# schematic-ebook-reader_v43.net
KiCad netlist of a schematic drawn in EAGLE
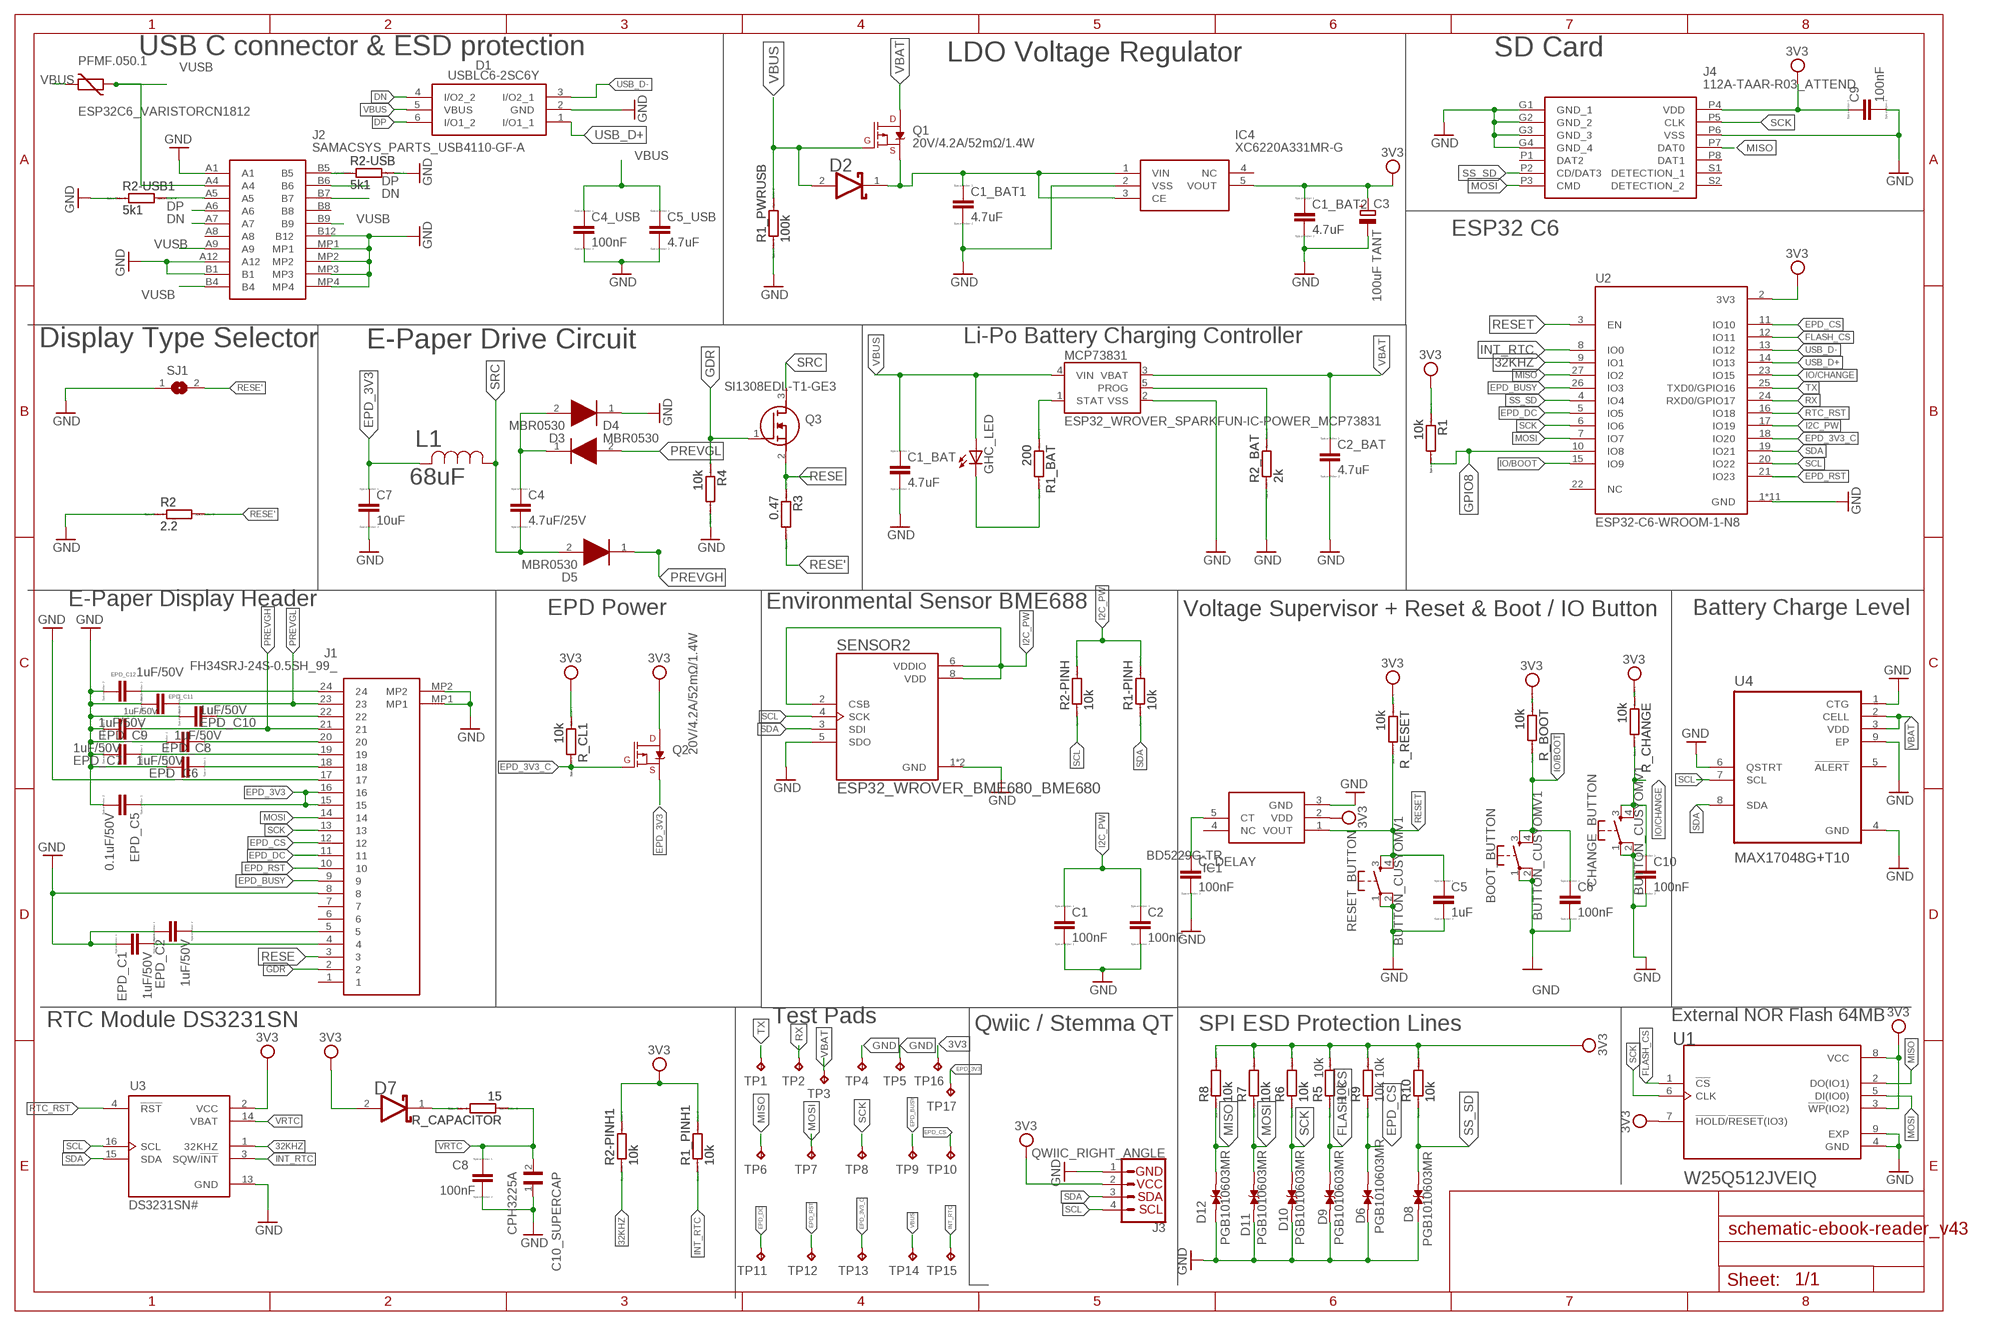
[diagram p0: schematic, sheet 1]

(export (version "E")
  (design (tool "Eeschema 10.0.6"))
  (components
    (comp (ref "BOOT_BUTTON")
      (value "BUTTON_CUSYOMV1")
      (footprint "eagle-import:MYBUTTON")
      (libsource (lib "eagle-import") (part "BUTTON_CUSYOMV1"))
    )
    (comp (ref "C1")
      (value "100nF")
      (footprint "eagle-import:ESP32_WROVER_EAGLE-LTSPICE_C0402")
      (libsource (lib "eagle-import") (part "ESP32_WROVER_EAGLE-LTSPICE_CC0402"))
    )
    (comp (ref "C1_BAT")
      (value "4.7uF")
      (footprint "eagle-import:ESP32_WROVER_EAGLE-LTSPICE_C0402")
      (libsource (lib "eagle-import") (part "ESP32_WROVER_EAGLE-LTSPICE_CC0402"))
    )
    (comp (ref "C1_BAT1")
      (value "4.7uF")
      (footprint "eagle-import:ESP32_WROVER_EAGLE-LTSPICE_C0402")
      (libsource (lib "eagle-import") (part "ESP32_WROVER_EAGLE-LTSPICE_CC0402"))
    )
    (comp (ref "C1_BAT2")
      (value "4.7uF")
      (footprint "eagle-import:ESP32_WROVER_EAGLE-LTSPICE_C0402")
      (libsource (lib "eagle-import") (part "ESP32_WROVER_EAGLE-LTSPICE_CC0402"))
    )
    (comp (ref "C2")
      (value "100nF")
      (footprint "eagle-import:ESP32_WROVER_EAGLE-LTSPICE_C0402")
      (libsource (lib "eagle-import") (part "ESP32_WROVER_EAGLE-LTSPICE_CC0402"))
    )
    (comp (ref "C2_BAT")
      (value "4.7uF")
      (footprint "eagle-import:ESP32_WROVER_EAGLE-LTSPICE_C0402")
      (libsource (lib "eagle-import") (part "ESP32_WROVER_EAGLE-LTSPICE_CC0402"))
    )
    (comp (ref "C3")
      (value "100uF TANT")
      (footprint "eagle-import:RCL_CT3528")
      (libsource (lib "eagle-import") (part "RCL_CPOL-EUCT3528"))
    )
    (comp (ref "C4")
      (value "4.7uF/25V")
      (footprint "eagle-import:ESP32_WROVER_EAGLE-LTSPICE_C0402")
      (libsource (lib "eagle-import") (part "ESP32_WROVER_EAGLE-LTSPICE_CC0402"))
    )
    (comp (ref "C4_USB")
      (value "100nF")
      (footprint "eagle-import:ESP32_WROVER_EAGLE-LTSPICE_C0402")
      (libsource (lib "eagle-import") (part "ESP32_WROVER_EAGLE-LTSPICE_CC0402"))
    )
    (comp (ref "C5")
      (value "1uF")
      (footprint "eagle-import:ESP32_WROVER_EAGLE-LTSPICE_C0402")
      (libsource (lib "eagle-import") (part "ESP32_WROVER_EAGLE-LTSPICE_CC0402"))
    )
    (comp (ref "C5_USB")
      (value "4.7uF")
      (footprint "eagle-import:ESP32_WROVER_EAGLE-LTSPICE_C0402")
      (libsource (lib "eagle-import") (part "ESP32_WROVER_EAGLE-LTSPICE_CC0402"))
    )
    (comp (ref "C6")
      (value "100nF")
      (footprint "eagle-import:ESP32_WROVER_EAGLE-LTSPICE_C0402")
      (libsource (lib "eagle-import") (part "ESP32_WROVER_EAGLE-LTSPICE_CC0402"))
    )
    (comp (ref "C7")
      (value "10uF")
      (footprint "eagle-import:ESP32_WROVER_EAGLE-LTSPICE_C0402")
      (libsource (lib "eagle-import") (part "ESP32_WROVER_EAGLE-LTSPICE_CC0402"))
    )
    (comp (ref "C8")
      (value "100nF")
      (footprint "eagle-import:ESP32_WROVER_EAGLE-LTSPICE_C0402")
      (libsource (lib "eagle-import") (part "ESP32_WROVER_EAGLE-LTSPICE_CC0402"))
    )
    (comp (ref "C9")
      (value "100nF")
      (footprint "eagle-import:ESP32_WROVER_EAGLE-LTSPICE_C0402")
      (libsource (lib "eagle-import") (part "ESP32_WROVER_EAGLE-LTSPICE_CC0402"))
    )
    (comp (ref "C10")
      (value "100nF")
      (footprint "eagle-import:ESP32_WROVER_EAGLE-LTSPICE_C0402")
      (libsource (lib "eagle-import") (part "ESP32_WROVER_EAGLE-LTSPICE_CC0402"))
    )
    (comp (ref "C10_SUPERCAP")
      (value "CPH3225A")
      (footprint "eagle-import:CAPCP3225X100N")
      (fields (field (name "MF") "Seiko Instruments"))
      (libsource (lib "eagle-import") (part "CPH3225A"))
    )
    (comp (ref "CHANGE_BUTTON")
      (value "BUTTON_CUSYOMV1")
      (footprint "eagle-import:MYBUTTON")
      (libsource (lib "eagle-import") (part "BUTTON_CUSYOMV1"))
    )
    (comp (ref "C_DELAY")
      (value "100nF")
      (footprint "eagle-import:ESP32_WROVER_EAGLE-LTSPICE_C0402")
      (libsource (lib "eagle-import") (part "ESP32_WROVER_EAGLE-LTSPICE_CC0402"))
    )
    (comp (ref "D1")
      (value "USBLC6-2SC6Y")
      (footprint "eagle-import:SOT95P280X145-6N")
      (fields (field (name "MF") "STMicroelectronics"))
      (libsource (lib "eagle-import") (part "USBLC6-2SC6Y"))
    )
    (comp (ref "D2")
      (value "ESP32_WROVER_AVX---SD0805S020S1R0_AVX_SD0805S020S1R0_0_0AVX_SD0805S020S1R0_0_0")
      (footprint "eagle-import:ESP32_WROVER_AVX---SD0805S020S1R0_AVX_SD0805S020S1R0_0")
      (fields
        (field (name "DIGIKEY_PART_NUMBER") "478-7800-1-ND")
        (field (name "MF") "AVX")
        (field (name "MOUSER_PART_NUMBER") "581-SD0805S020S1R0")
      )
      (libsource (lib "eagle-import") (part "ESP32_WROVER_AVX---SD0805S020S1R0_AVX_SD0805S020S1R0_0_0AVX_SD0805S020S1R0_0_0"))
    )
    (comp (ref "D3")
      (value "MBR0530")
      (footprint "eagle-import:SOD3716X135N")
      (fields (field (name "MF") "ON Semiconductor"))
      (libsource (lib "eagle-import") (part "MBR0530"))
    )
    (comp (ref "D4")
      (value "MBR0530")
      (footprint "eagle-import:SOD3716X135N")
      (fields (field (name "MF") "ON Semiconductor"))
      (libsource (lib "eagle-import") (part "MBR0530"))
    )
    (comp (ref "D5")
      (value "MBR0530")
      (footprint "eagle-import:SOD3716X135N")
      (fields (field (name "MF") "ON Semiconductor"))
      (libsource (lib "eagle-import") (part "MBR0530"))
    )
    (comp (ref "D6")
      (value "PGB1010603MR")
      (footprint "eagle-import:DIOC1608X36N")
      (fields (field (name "MF") "Littelfuse Inc."))
      (libsource (lib "eagle-import") (part "PGB1010603MR"))
    )
    (comp (ref "D7")
      (value "ESP32_WROVER_AVX---SD0805S020S1R0_AVX_SD0805S020S1R0_0_0AVX_SD0805S020S1R0_0_0")
      (footprint "eagle-import:ESP32_WROVER_AVX---SD0805S020S1R0_AVX_SD0805S020S1R0_0")
      (fields
        (field (name "DIGIKEY_PART_NUMBER") "478-7800-1-ND")
        (field (name "MF") "AVX")
        (field (name "MOUSER_PART_NUMBER") "581-SD0805S020S1R0")
      )
      (libsource (lib "eagle-import") (part "ESP32_WROVER_AVX---SD0805S020S1R0_AVX_SD0805S020S1R0_0_0AVX_SD0805S020S1R0_0_0"))
    )
    (comp (ref "D8")
      (value "PGB1010603MR")
      (footprint "eagle-import:DIOC1608X36N")
      (fields (field (name "MF") "Littelfuse Inc."))
      (libsource (lib "eagle-import") (part "PGB1010603MR"))
    )
    (comp (ref "D9")
      (value "PGB1010603MR")
      (footprint "eagle-import:DIOC1608X36N")
      (fields (field (name "MF") "Littelfuse Inc."))
      (libsource (lib "eagle-import") (part "PGB1010603MR"))
    )
    (comp (ref "D10")
      (value "PGB1010603MR")
      (footprint "eagle-import:DIOC1608X36N")
      (fields (field (name "MF") "Littelfuse Inc."))
      (libsource (lib "eagle-import") (part "PGB1010603MR"))
    )
    (comp (ref "D11")
      (value "PGB1010603MR")
      (footprint "eagle-import:DIOC1608X36N")
      (fields (field (name "MF") "Littelfuse Inc."))
      (libsource (lib "eagle-import") (part "PGB1010603MR"))
    )
    (comp (ref "D12")
      (value "PGB1010603MR")
      (footprint "eagle-import:DIOC1608X36N")
      (fields (field (name "MF") "Littelfuse Inc."))
      (libsource (lib "eagle-import") (part "PGB1010603MR"))
    )
    (comp (ref "EPD_C1")
      (value "1uF/50V")
      (footprint "eagle-import:ESP32_WROVER_EAGLE-LTSPICE_C0402")
      (libsource (lib "eagle-import") (part "ESP32_WROVER_EAGLE-LTSPICE_CC0402"))
    )
    (comp (ref "EPD_C2")
      (value "1uF/50V")
      (footprint "eagle-import:ESP32_WROVER_EAGLE-LTSPICE_C0402")
      (libsource (lib "eagle-import") (part "ESP32_WROVER_EAGLE-LTSPICE_CC0402"))
    )
    (comp (ref "EPD_C5")
      (value "0.1uF/50V")
      (footprint "eagle-import:ESP32_WROVER_EAGLE-LTSPICE_C0402")
      (libsource (lib "eagle-import") (part "ESP32_WROVER_EAGLE-LTSPICE_CC0402"))
    )
    (comp (ref "EPD_C6")
      (value "1uF/50V")
      (footprint "eagle-import:ESP32_WROVER_EAGLE-LTSPICE_C0402")
      (libsource (lib "eagle-import") (part "ESP32_WROVER_EAGLE-LTSPICE_CC0402"))
    )
    (comp (ref "EPD_C7")
      (value "1uF/50V")
      (footprint "eagle-import:ESP32_WROVER_EAGLE-LTSPICE_C0402")
      (libsource (lib "eagle-import") (part "ESP32_WROVER_EAGLE-LTSPICE_CC0402"))
    )
    (comp (ref "EPD_C8")
      (value "1uF/50V")
      (footprint "eagle-import:ESP32_WROVER_EAGLE-LTSPICE_C0402")
      (libsource (lib "eagle-import") (part "ESP32_WROVER_EAGLE-LTSPICE_CC0402"))
    )
    (comp (ref "EPD_C9")
      (value "1uF/50V")
      (footprint "eagle-import:ESP32_WROVER_EAGLE-LTSPICE_C0402")
      (libsource (lib "eagle-import") (part "ESP32_WROVER_EAGLE-LTSPICE_CC0402"))
    )
    (comp (ref "EPD_C10")
      (value "1uF/50V")
      (footprint "eagle-import:ESP32_WROVER_EAGLE-LTSPICE_C0402")
      (libsource (lib "eagle-import") (part "ESP32_WROVER_EAGLE-LTSPICE_CC0402"))
    )
    (comp (ref "EPD_C11")
      (value "1uF/50V")
      (footprint "eagle-import:ESP32_WROVER_EAGLE-LTSPICE_C0402")
      (libsource (lib "eagle-import") (part "ESP32_WROVER_EAGLE-LTSPICE_CC0402"))
    )
    (comp (ref "EPD_C12")
      (value "1uF/50V")
      (footprint "eagle-import:ESP32_WROVER_EAGLE-LTSPICE_C0402")
      (libsource (lib "eagle-import") (part "ESP32_WROVER_EAGLE-LTSPICE_CC0402"))
    )
    (comp (ref "GHC_LED")
      (value "ADAFRUIT_LEDCHIP-LED0603")
      (footprint "eagle-import:ADAFRUIT_CHIP-LED0603")
      (libsource (lib "eagle-import") (part "ADAFRUIT_LEDCHIP-LED0603"))
    )
    (comp (ref "IC1")
      (value "BD5229G-TR")
      (footprint "eagle-import:SOT95P280X125-5N")
      (fields (field (name "MOUSER_PART_NUMBER") "755-BD5229G-TR"))
      (libsource (lib "eagle-import") (part "BD5229G-TR"))
    )
    (comp (ref "IC4")
      (value "XC6220A331MR-G")
      (footprint "eagle-import:SOT95P280X120-5N")
      (fields (field (name "MOUSER_PART_NUMBER") "865-XC6220A331MR-G"))
      (libsource (lib "eagle-import") (part "XC6220A331MR-G"))
    )
    (comp (ref "J1")
      (value "FH34SRJ-24S-0.5SH_99_")
      (footprint "eagle-import:FH34SRJ24S05SH99")
      (fields
        (field (name "MANUFACTURER_PART_NUMBER") "FH34SRJ-24S-0.5SH(99)")
        (field (name "MOUSER_PART_NUMBER") "798-FH34SRJ24S05SH99")
      )
      (libsource (lib "eagle-import") (part "FH34SRJ-24S-0.5SH_99_"))
    )
    (comp (ref "J2")
      (value "SAMACSYS_PARTS_USB4110-GF-A")
      (footprint "eagle-import:SAMACSYS_PARTS_USB4110GFA")
      (fields
        (field (name "MANUFACTURER_PART_NUMBER") "USB4110-GF-A")
        (field (name "MOUSER_PART_NUMBER") "640-USB4110-GF-A")
      )
      (libsource (lib "eagle-import") (part "SAMACSYS_PARTS_USB4110-GF-A"))
    )
    (comp (ref "J3")
      (value "QWIIC_RIGHT_ANGLE")
      (footprint "eagle-import:JST04_1MM_RA")
      (libsource (lib "eagle-import") (part "QWIIC_CONNECTORJS-1MM"))
    )
    (comp (ref "J4")
      (value "112A-TAAR-R03_ATTEND")
      (footprint "eagle-import:112ATAARR03ATTEND")
      (fields (field (name "MANUFACTURER_PART_NUMBER") "112A-TAAR-R03 ATTEND"))
      (libsource (lib "eagle-import") (part "112A-TAAR-R03_ATTEND"))
    )
    (comp (ref "L1")
      (value "68uF")
      (footprint "eagle-import:IND_4828-WE-TPC_WRE")
      (fields
        (field (name "MANUFACTURER_PART_NUMBER") "744043680")
        (field (name "COPYRIGHT") "Copyright (C) 2024 Ultra Librarian. All rights reserved.")
      )
      (libsource (lib "eagle-import") (part "744043680IND_4828-WE-TPC_WRE"))
    )
    (comp (ref "MCP73831")
      (value "ESP32_WROVER_SPARKFUN-IC-POWER_MCP73831")
      (footprint "eagle-import:ESP32_WROVER_SPARKFUN-IC-POWER_SOT23-5")
      (libsource (lib "eagle-import") (part "ESP32_WROVER_SPARKFUN-IC-POWER_MCP73831"))
    )
    (comp (ref "PFMF.050.1")
      (value "ESP32C6_VARISTORCN1812")
      (footprint "eagle-import:ESP32C6_VARISTOR_CT_CN1812")
      (libsource (lib "eagle-import") (part "ESP32C6_VARISTORCN1812"))
    )
    (comp (ref "Q1")
      (value "20V/4.2A/52mΩ/1.4W")
      (footprint "eagle-import:ESP32_WROVER_SPARKFUN-DISCRETESEMI_SOT23-3")
      (libsource (lib "eagle-import") (part "ESP32_WROVER_SPARKFUN-DISCRETESEMI_MOSFET_PCH-DMG2305UX-7"))
    )
    (comp (ref "Q2")
      (value "20V/4.2A/52mΩ/1.4W")
      (footprint "eagle-import:ESP32_WROVER_SPARKFUN-DISCRETESEMI_SOT23-3")
      (libsource (lib "eagle-import") (part "ESP32_WROVER_SPARKFUN-DISCRETESEMI_MOSFET_PCH-DMG2305UX-7"))
    )
    (comp (ref "Q3")
      (value "SI1308EDL-T1-GE3")
      (footprint "eagle-import:SOT65P210X110-3N")
      (fields (field (name "MF") "Vishay Siliconix"))
      (libsource (lib "eagle-import") (part "SI1308EDL-T1-GE3"))
    )
    (comp (ref "R1")
      (value "10k")
      (footprint "eagle-import:ESP32_WROVER_EAGLE-LTSPICE_C0402")
      (libsource (lib "eagle-import") (part "ESP32_WROVER_EAGLE-LTSPICE_RR0402"))
    )
    (comp (ref "R1-PINH")
      (value "10k")
      (footprint "eagle-import:ESP32_WROVER_EAGLE-LTSPICE_C0402")
      (libsource (lib "eagle-import") (part "ESP32_WROVER_EAGLE-LTSPICE_RR0402"))
    )
    (comp (ref "R1_BAT")
      (value "200")
      (footprint "eagle-import:ESP32_WROVER_EAGLE-LTSPICE_C0402")
      (libsource (lib "eagle-import") (part "ESP32_WROVER_EAGLE-LTSPICE_RR0402"))
    )
    (comp (ref "R1_PINH1")
      (value "10k")
      (footprint "eagle-import:ESP32_WROVER_EAGLE-LTSPICE_C0402")
      (libsource (lib "eagle-import") (part "ESP32_WROVER_EAGLE-LTSPICE_RR0402"))
    )
    (comp (ref "R1_PWRUSB")
      (value "100k")
      (footprint "eagle-import:ESP32_WROVER_EAGLE-LTSPICE_C0402")
      (libsource (lib "eagle-import") (part "ESP32_WROVER_EAGLE-LTSPICE_RR0402"))
    )
    (comp (ref "R2")
      (value "2.2")
      (footprint "eagle-import:ESP32_WROVER_EAGLE-LTSPICE_C0402")
      (libsource (lib "eagle-import") (part "ESP32_WROVER_EAGLE-LTSPICE_RR0402"))
    )
    (comp (ref "R2-PINH")
      (value "10k")
      (footprint "eagle-import:ESP32_WROVER_EAGLE-LTSPICE_C0402")
      (libsource (lib "eagle-import") (part "ESP32_WROVER_EAGLE-LTSPICE_RR0402"))
    )
    (comp (ref "R2-PINH1")
      (value "10k")
      (footprint "eagle-import:ESP32_WROVER_EAGLE-LTSPICE_C0402")
      (libsource (lib "eagle-import") (part "ESP32_WROVER_EAGLE-LTSPICE_RR0402"))
    )
    (comp (ref "R2-USB")
      (value "5k1")
      (footprint "eagle-import:ESP32_WROVER_EAGLE-LTSPICE_C0402")
      (libsource (lib "eagle-import") (part "ESP32_WROVER_EAGLE-LTSPICE_RR0402"))
    )
    (comp (ref "R2-USB1")
      (value "5k1")
      (footprint "eagle-import:ESP32_WROVER_EAGLE-LTSPICE_C0402")
      (libsource (lib "eagle-import") (part "ESP32_WROVER_EAGLE-LTSPICE_RR0402"))
    )
    (comp (ref "R2_BAT")
      (value "2k")
      (footprint "eagle-import:ESP32_WROVER_EAGLE-LTSPICE_C0402")
      (libsource (lib "eagle-import") (part "ESP32_WROVER_EAGLE-LTSPICE_RR0402"))
    )
    (comp (ref "R3")
      (value "0.47")
      (footprint "eagle-import:ESP32_WROVER_EAGLE-LTSPICE_C0402")
      (libsource (lib "eagle-import") (part "ESP32_WROVER_EAGLE-LTSPICE_RR0402"))
    )
    (comp (ref "R4")
      (value "10k")
      (footprint "eagle-import:ESP32_WROVER_EAGLE-LTSPICE_C0402")
      (libsource (lib "eagle-import") (part "ESP32_WROVER_EAGLE-LTSPICE_RR0402"))
    )
    (comp (ref "R5")
      (value "10k")
      (footprint "eagle-import:ESP32_WROVER_EAGLE-LTSPICE_C0402")
      (libsource (lib "eagle-import") (part "ESP32_WROVER_EAGLE-LTSPICE_RR0402"))
    )
    (comp (ref "R6")
      (value "10k")
      (footprint "eagle-import:ESP32_WROVER_EAGLE-LTSPICE_C0402")
      (libsource (lib "eagle-import") (part "ESP32_WROVER_EAGLE-LTSPICE_RR0402"))
    )
    (comp (ref "R7")
      (value "10k")
      (footprint "eagle-import:ESP32_WROVER_EAGLE-LTSPICE_C0402")
      (libsource (lib "eagle-import") (part "ESP32_WROVER_EAGLE-LTSPICE_RR0402"))
    )
    (comp (ref "R8")
      (value "10k")
      (footprint "eagle-import:ESP32_WROVER_EAGLE-LTSPICE_C0402")
      (libsource (lib "eagle-import") (part "ESP32_WROVER_EAGLE-LTSPICE_RR0402"))
    )
    (comp (ref "R9")
      (value "10k")
      (footprint "eagle-import:ESP32_WROVER_EAGLE-LTSPICE_C0402")
      (libsource (lib "eagle-import") (part "ESP32_WROVER_EAGLE-LTSPICE_RR0402"))
    )
    (comp (ref "R10")
      (value "10k")
      (footprint "eagle-import:ESP32_WROVER_EAGLE-LTSPICE_C0402")
      (libsource (lib "eagle-import") (part "ESP32_WROVER_EAGLE-LTSPICE_RR0402"))
    )
    (comp (ref "RESET_BUTTON")
      (value "BUTTON_CUSYOMV1")
      (footprint "eagle-import:MYBUTTON")
      (libsource (lib "eagle-import") (part "BUTTON_CUSYOMV1"))
    )
    (comp (ref "R_BOOT")
      (value "10k")
      (footprint "eagle-import:ESP32_WROVER_EAGLE-LTSPICE_C0402")
      (libsource (lib "eagle-import") (part "ESP32_WROVER_EAGLE-LTSPICE_RR0402"))
    )
    (comp (ref "R_CAPACITOR")
      (value "15")
      (footprint "eagle-import:ESP32_WROVER_EAGLE-LTSPICE_C0402")
      (libsource (lib "eagle-import") (part "ESP32_WROVER_EAGLE-LTSPICE_RR0402"))
    )
    (comp (ref "R_CHANGE")
      (value "10k")
      (footprint "eagle-import:ESP32_WROVER_EAGLE-LTSPICE_C0402")
      (libsource (lib "eagle-import") (part "ESP32_WROVER_EAGLE-LTSPICE_RR0402"))
    )
    (comp (ref "R_CL1")
      (value "10k")
      (footprint "eagle-import:ESP32_WROVER_EAGLE-LTSPICE_C0402")
      (libsource (lib "eagle-import") (part "ESP32_WROVER_EAGLE-LTSPICE_RR0402"))
    )
    (comp (ref "R_RESET")
      (value "10k")
      (footprint "eagle-import:ESP32_WROVER_EAGLE-LTSPICE_C0402")
      (libsource (lib "eagle-import") (part "ESP32_WROVER_EAGLE-LTSPICE_RR0402"))
    )
    (comp (ref "SENSOR2")
      (value "ESP32_WROVER_BME680_BME680")
      (footprint "eagle-import:ESP32_WROVER_BME680_PSON80P300X300X100-8N")
      (fields (field (name "MF") "Bosch Sensortec") (field (name "MP") "BME680"))
      (libsource (lib "eagle-import") (part "ESP32_WROVER_BME680_BME680"))
    )
    (comp (ref "SJ1") (value "SJ") (footprint "eagle-import:SJ") (libsource (lib "eagle-import") (part "SJ")))
    (comp (ref "TP1")
      (value "TPTP20R")
      (footprint "eagle-import:TP20R")
      (libsource (lib "eagle-import") (part "TPTP20R"))
    )
    (comp (ref "TP2")
      (value "TPTP20R")
      (footprint "eagle-import:TP20R")
      (libsource (lib "eagle-import") (part "TPTP20R"))
    )
    (comp (ref "TP3")
      (value "TPTP20R")
      (footprint "eagle-import:TP20R")
      (libsource (lib "eagle-import") (part "TPTP20R"))
    )
    (comp (ref "TP4")
      (value "TPTP20R")
      (footprint "eagle-import:TP20R")
      (libsource (lib "eagle-import") (part "TPTP20R"))
    )
    (comp (ref "TP5")
      (value "TPTP20R")
      (footprint "eagle-import:TP20R")
      (libsource (lib "eagle-import") (part "TPTP20R"))
    )
    (comp (ref "TP6")
      (value "TPTP20R")
      (footprint "eagle-import:TP20R")
      (libsource (lib "eagle-import") (part "TPTP20R"))
    )
    (comp (ref "TP7")
      (value "TPTP20R")
      (footprint "eagle-import:TP20R")
      (libsource (lib "eagle-import") (part "TPTP20R"))
    )
    (comp (ref "TP8")
      (value "TPTP20R")
      (footprint "eagle-import:TP20R")
      (libsource (lib "eagle-import") (part "TPTP20R"))
    )
    (comp (ref "TP9")
      (value "TPTP20R")
      (footprint "eagle-import:TP20R")
      (libsource (lib "eagle-import") (part "TPTP20R"))
    )
    (comp (ref "TP10")
      (value "TPTP20R")
      (footprint "eagle-import:TP20R")
      (libsource (lib "eagle-import") (part "TPTP20R"))
    )
    (comp (ref "TP11")
      (value "TPTP20R")
      (footprint "eagle-import:TP20R")
      (libsource (lib "eagle-import") (part "TPTP20R"))
    )
    (comp (ref "TP12")
      (value "TPTP20R")
      (footprint "eagle-import:TP20R")
      (libsource (lib "eagle-import") (part "TPTP20R"))
    )
    (comp (ref "TP13")
      (value "TPTP20R")
      (footprint "eagle-import:TP20R")
      (libsource (lib "eagle-import") (part "TPTP20R"))
    )
    (comp (ref "TP14")
      (value "TPTP20R")
      (footprint "eagle-import:TP20R")
      (libsource (lib "eagle-import") (part "TPTP20R"))
    )
    (comp (ref "TP15")
      (value "TPTP20R")
      (footprint "eagle-import:TP20R")
      (libsource (lib "eagle-import") (part "TPTP20R"))
    )
    (comp (ref "TP16")
      (value "TPTP20R")
      (footprint "eagle-import:TP20R")
      (libsource (lib "eagle-import") (part "TPTP20R"))
    )
    (comp (ref "TP17")
      (value "TPTP20R")
      (footprint "eagle-import:TP20R")
      (libsource (lib "eagle-import") (part "TPTP20R"))
    )
    (comp (ref "U1")
      (value "W25Q512JVEIQ")
      (footprint "eagle-import:SON127P600X800X80-9N")
      (fields (field (name "MF") "Winbond Electronics"))
      (libsource (lib "eagle-import") (part "W25Q512JVEIQ"))
    )
    (comp (ref "U2")
      (value "ESP32-C6-WROOM-1-N8")
      (footprint "eagle-import:XCVR_ESP32-C6-WROOM-1-N8")
      (fields (field (name "MF") "Espressif Systems"))
      (libsource (lib "eagle-import") (part "ESP32-C6-WROOM-1-N8"))
    )
    (comp (ref "U3")
      (value "DS3231SN#")
      (footprint "eagle-import:SOIC127P1032X265-16N")
      (fields (field (name "MF") "Analog Devices"))
      (libsource (lib "eagle-import") (part "DS3231SN#"))
    )
    (comp (ref "U4")
      (value "MAX17048G+T10")
      (footprint "eagle-import:SON50P200X200X80-9N")
      (fields (field (name "MF") "Analog Devices"))
      (libsource (lib "eagle-import") (part "MAX17048G+T10"))
    )
  )
  (nets
    (net (code "1") (name "/VUSB") (class "Default")
      (node (ref "J2") (pin "A4") (pinfunction "A4_A4") (pintype "bidirectional"))
      (node (ref "J2") (pin "A9") (pinfunction "A9_A9") (pintype "bidirectional"))
      (node (ref "J2") (pin "B4") (pinfunction "B4_B4") (pintype "bidirectional"))
      (node (ref "J2") (pin "B9") (pinfunction "B9_B9") (pintype "bidirectional"))
      (node (ref "PFMF.050.1") (pin "1") (pinfunction "1_1") (pintype "passive"))
    )
    (net (code "2") (name "3V3") (class "Default")
      (node (ref "C1_BAT2") (pin "1") (pinfunction "1_1") (pintype "passive"))
      (node (ref "C3") (pin "+") (pinfunction "+_+") (pintype "passive"))
      (node (ref "C9") (pin "1") (pinfunction "1_1") (pintype "passive"))
      (node (ref "D7") (pin "2") (pinfunction "ANODE_2") (pintype "bidirectional"))
      (node (ref "IC1") (pin "2") (pinfunction "VDD_2") (pintype "bidirectional"))
      (node (ref "IC4") (pin "5") (pinfunction "VOUT_5") (pintype "bidirectional"))
      (node (ref "J3") (pin "2") (pinfunction "2_2") (pintype "power_in"))
      (node (ref "J4") (pin "P4") (pinfunction "VDD_P4") (pintype "bidirectional"))
      (node (ref "Q2") (pin "3") (pinfunction "D_3") (pintype "bidirectional"))
      (node (ref "R1") (pin "1") (pinfunction "1_1") (pintype "passive"))
      (node (ref "R10") (pin "2") (pinfunction "2_2") (pintype "passive"))
      (node (ref "R1_PINH1") (pin "2") (pinfunction "2_2") (pintype "passive"))
      (node (ref "R2-PINH1") (pin "2") (pinfunction "2_2") (pintype "passive"))
      (node (ref "R5") (pin "2") (pinfunction "2_2") (pintype "passive"))
      (node (ref "R6") (pin "2") (pinfunction "2_2") (pintype "passive"))
      (node (ref "R7") (pin "2") (pinfunction "2_2") (pintype "passive"))
      (node (ref "R8") (pin "2") (pinfunction "2_2") (pintype "passive"))
      (node (ref "R9") (pin "2") (pinfunction "2_2") (pintype "passive"))
      (node (ref "R_BOOT") (pin "1") (pinfunction "1_1") (pintype "passive"))
      (node (ref "R_CHANGE") (pin "1") (pinfunction "1_1") (pintype "passive"))
      (node (ref "R_CL1") (pin "1") (pinfunction "1_1") (pintype "passive"))
      (node (ref "R_RESET") (pin "1") (pinfunction "1_1") (pintype "passive"))
      (node (ref "TP16") (pin "TP") (pinfunction "TP_TP") (pintype "input"))
      (node (ref "U1") (pin "3") (pinfunction "~{WP}(IO2)_3") (pintype "bidirectional"))
      (node (ref "U1") (pin "7") (pinfunction "~{HOLD}/~{RESET}(IO3)_7") (pintype "bidirectional"))
      (node (ref "U1") (pin "8") (pinfunction "VCC_8") (pintype "power_in"))
      (node (ref "U2") (pin "2") (pinfunction "3V3_2") (pintype "power_in"))
      (node (ref "U3") (pin "2") (pinfunction "VCC_2") (pintype "power_in"))
    )
    (net (code "3") (name "32KHZ") (class "Default")
      (node (ref "R2-PINH1") (pin "1") (pinfunction "1_1") (pintype "passive"))
      (node (ref "U2") (pin "9") (pinfunction "IO1_9") (pintype "bidirectional"))
      (node (ref "U3") (pin "1") (pinfunction "32KHZ_1") (pintype "output"))
    )
    (net (code "4") (name "DN") (class "Default")
      (node (ref "D1") (pin "4") (pinfunction "I/O2_2_4") (pintype "bidirectional"))
      (node (ref "J2") (pin "A7") (pinfunction "A7_A7") (pintype "bidirectional"))
      (node (ref "J2") (pin "B7") (pinfunction "B7_B7") (pintype "bidirectional"))
    )
    (net (code "5") (name "DP") (class "Default")
      (node (ref "D1") (pin "6") (pinfunction "I/O1_2_6") (pintype "bidirectional"))
      (node (ref "J2") (pin "A6") (pinfunction "A6_A6") (pintype "bidirectional"))
      (node (ref "J2") (pin "B6") (pinfunction "B6_B6") (pintype "bidirectional"))
    )
    (net (code "6") (name "EPD_3V3") (class "Default")
      (node (ref "C7") (pin "1") (pinfunction "1_1") (pintype "passive"))
      (node (ref "EPD_C5") (pin "1") (pinfunction "1_1") (pintype "passive"))
      (node (ref "J1") (pin "15") (pinfunction "15_15") (pintype "bidirectional"))
      (node (ref "J1") (pin "16") (pinfunction "16_16") (pintype "bidirectional"))
      (node (ref "L1") (pin "2") (pinfunction "2_2") (pintype "passive"))
      (node (ref "Q2") (pin "2") (pinfunction "S_2") (pintype "bidirectional"))
      (node (ref "TP17") (pin "TP") (pinfunction "TP_TP") (pintype "input"))
    )
    (net (code "7") (name "EPD_3V3_C") (class "Default")
      (node (ref "Q2") (pin "1") (pinfunction "G_1") (pintype "bidirectional"))
      (node (ref "R_CL1") (pin "2") (pinfunction "2_2") (pintype "passive"))
      (node (ref "TP13") (pin "TP") (pinfunction "TP_TP") (pintype "input"))
      (node (ref "U2") (pin "18") (pinfunction "IO20_18") (pintype "bidirectional"))
    )
    (net (code "8") (name "EPD_BUSY") (class "Default")
      (node (ref "J1") (pin "9") (pinfunction "9_9") (pintype "bidirectional"))
      (node (ref "TP9") (pin "TP") (pinfunction "TP_TP") (pintype "input"))
      (node (ref "U2") (pin "26") (pinfunction "IO3_26") (pintype "bidirectional"))
    )
    (net (code "9") (name "EPD_CS") (class "Default")
      (node (ref "D6") (pin "2") (pinfunction "2_2") (pintype "passive"))
      (node (ref "J1") (pin "12") (pinfunction "12_12") (pintype "bidirectional"))
      (node (ref "R9") (pin "1") (pinfunction "1_1") (pintype "passive"))
      (node (ref "TP10") (pin "TP") (pinfunction "TP_TP") (pintype "input"))
      (node (ref "U2") (pin "11") (pinfunction "IO10_11") (pintype "bidirectional"))
    )
    (net (code "10") (name "EPD_DC") (class "Default")
      (node (ref "J1") (pin "11") (pinfunction "11_11") (pintype "bidirectional"))
      (node (ref "TP11") (pin "TP") (pinfunction "TP_TP") (pintype "input"))
      (node (ref "U2") (pin "5") (pinfunction "IO5_5") (pintype "bidirectional"))
    )
    (net (code "11") (name "EPD_RST") (class "Default")
      (node (ref "J1") (pin "10") (pinfunction "10_10") (pintype "bidirectional"))
      (node (ref "TP12") (pin "TP") (pinfunction "TP_TP") (pintype "input"))
      (node (ref "U2") (pin "21") (pinfunction "IO23_21") (pintype "bidirectional"))
    )
    (net (code "12") (name "FLASH_CS") (class "Default")
      (node (ref "D9") (pin "2") (pinfunction "2_2") (pintype "passive"))
      (node (ref "R5") (pin "1") (pinfunction "1_1") (pintype "passive"))
      (node (ref "U1") (pin "1") (pinfunction "~{CS}_1") (pintype "input"))
      (node (ref "U2") (pin "12") (pinfunction "IO11_12") (pintype "bidirectional"))
    )
    (net (code "13") (name "GDR") (class "Default")
      (node (ref "J1") (pin "2") (pinfunction "2_2") (pintype "bidirectional"))
      (node (ref "Q3") (pin "1") (pinfunction "G_1") (pintype "bidirectional"))
      (node (ref "R4") (pin "1") (pinfunction "1_1") (pintype "passive"))
    )
    (net (code "14") (name "GND") (class "Default")
      (node (ref "BOOT_BUTTON") (pin "1") (pinfunction "1_1") (pintype "passive"))
      (node (ref "BOOT_BUTTON") (pin "2") (pinfunction "2_2") (pintype "passive"))
      (node (ref "C1") (pin "2") (pinfunction "2_2") (pintype "passive"))
      (node (ref "C10") (pin "2") (pinfunction "2_2") (pintype "passive"))
      (node (ref "C10_SUPERCAP") (pin "1") (pinfunction "1_1") (pintype "passive"))
      (node (ref "C1_BAT") (pin "2") (pinfunction "2_2") (pintype "passive"))
      (node (ref "C1_BAT1") (pin "2") (pinfunction "2_2") (pintype "passive"))
      (node (ref "C1_BAT2") (pin "2") (pinfunction "2_2") (pintype "passive"))
      (node (ref "C2") (pin "2") (pinfunction "2_2") (pintype "passive"))
      (node (ref "C2_BAT") (pin "2") (pinfunction "2_2") (pintype "passive"))
      (node (ref "C3") (pin "-") (pinfunction "-_-") (pintype "passive"))
      (node (ref "C4_USB") (pin "2") (pinfunction "2_2") (pintype "passive"))
      (node (ref "C5") (pin "2") (pinfunction "2_2") (pintype "passive"))
      (node (ref "C5_USB") (pin "2") (pinfunction "2_2") (pintype "passive"))
      (node (ref "C6") (pin "2") (pinfunction "2_2") (pintype "passive"))
      (node (ref "C7") (pin "2") (pinfunction "2_2") (pintype "passive"))
      (node (ref "C8") (pin "2") (pinfunction "2_2") (pintype "passive"))
      (node (ref "C9") (pin "2") (pinfunction "2_2") (pintype "passive"))
      (node (ref "CHANGE_BUTTON") (pin "1") (pinfunction "1_1") (pintype "passive"))
      (node (ref "CHANGE_BUTTON") (pin "2") (pinfunction "2_2") (pintype "passive"))
      (node (ref "C_DELAY") (pin "2") (pinfunction "2_2") (pintype "passive"))
      (node (ref "D1") (pin "2") (pinfunction "GND_2") (pintype "bidirectional"))
      (node (ref "D10") (pin "1") (pinfunction "1_1") (pintype "passive"))
      (node (ref "D11") (pin "1") (pinfunction "1_1") (pintype "passive"))
      (node (ref "D12") (pin "1") (pinfunction "1_1") (pintype "passive"))
      (node (ref "D3") (pin "1") (pinfunction "K_1") (pintype "bidirectional"))
      (node (ref "D6") (pin "1") (pinfunction "1_1") (pintype "passive"))
      (node (ref "D8") (pin "1") (pinfunction "1_1") (pintype "passive"))
      (node (ref "D9") (pin "1") (pinfunction "1_1") (pintype "passive"))
      (node (ref "EPD_C1") (pin "1") (pinfunction "1_1") (pintype "passive"))
      (node (ref "EPD_C10") (pin "2") (pinfunction "2_2") (pintype "passive"))
      (node (ref "EPD_C11") (pin "2") (pinfunction "2_2") (pintype "passive"))
      (node (ref "EPD_C12") (pin "2") (pinfunction "2_2") (pintype "passive"))
      (node (ref "EPD_C2") (pin "1") (pinfunction "1_1") (pintype "passive"))
      (node (ref "EPD_C5") (pin "2") (pinfunction "2_2") (pintype "passive"))
      (node (ref "EPD_C6") (pin "2") (pinfunction "2_2") (pintype "passive"))
      (node (ref "EPD_C7") (pin "2") (pinfunction "2_2") (pintype "passive"))
      (node (ref "EPD_C8") (pin "2") (pinfunction "2_2") (pintype "passive"))
      (node (ref "EPD_C9") (pin "2") (pinfunction "2_2") (pintype "passive"))
      (node (ref "IC1") (pin "3") (pinfunction "GND_3") (pintype "bidirectional"))
      (node (ref "IC4") (pin "2") (pinfunction "VSS_2") (pintype "bidirectional"))
      (node (ref "J1") (pin "17") (pinfunction "17_17") (pintype "bidirectional"))
      (node (ref "J1") (pin "8") (pinfunction "8_8") (pintype "bidirectional"))
      (node (ref "J1") (pin "MP1") (pinfunction "MP1_MP1") (pintype "bidirectional"))
      (node (ref "J1") (pin "MP2") (pinfunction "MP2_MP2") (pintype "bidirectional"))
      (node (ref "J2") (pin "A1") (pinfunction "A1_A1") (pintype "bidirectional"))
      (node (ref "J2") (pin "A12") (pinfunction "A12_A12") (pintype "bidirectional"))
      (node (ref "J2") (pin "B1") (pinfunction "B1_B1") (pintype "bidirectional"))
      (node (ref "J2") (pin "B12") (pinfunction "B12_B12") (pintype "bidirectional"))
      (node (ref "J2") (pin "MP1") (pinfunction "MP1_MP1") (pintype "bidirectional"))
      (node (ref "J2") (pin "MP2") (pinfunction "MP2_MP2") (pintype "bidirectional"))
      (node (ref "J2") (pin "MP3") (pinfunction "MP3_MP3") (pintype "bidirectional"))
      (node (ref "J2") (pin "MP4") (pinfunction "MP4_MP4") (pintype "bidirectional"))
      (node (ref "J3") (pin "1") (pinfunction "1_1") (pintype "power_in"))
      (node (ref "J4") (pin "G1") (pinfunction "GND_1_G1") (pintype "bidirectional"))
      (node (ref "J4") (pin "G2") (pinfunction "GND_2_G2") (pintype "bidirectional"))
      (node (ref "J4") (pin "G3") (pinfunction "GND_3_G3") (pintype "bidirectional"))
      (node (ref "J4") (pin "G4") (pinfunction "GND_4_G4") (pintype "bidirectional"))
      (node (ref "J4") (pin "P6") (pinfunction "VSS_P6") (pintype "bidirectional"))
      (node (ref "MCP73831") (pin "2") (pinfunction "VSS_2") (pintype "power_in"))
      (node (ref "R1_PWRUSB") (pin "1") (pinfunction "1_1") (pintype "passive"))
      (node (ref "R2") (pin "1") (pinfunction "1_1") (pintype "passive"))
      (node (ref "R2-USB") (pin "2") (pinfunction "2_2") (pintype "passive"))
      (node (ref "R2-USB1") (pin "1") (pinfunction "1_1") (pintype "passive"))
      (node (ref "R2_BAT") (pin "1") (pinfunction "1_1") (pintype "passive"))
      (node (ref "R4") (pin "2") (pinfunction "2_2") (pintype "passive"))
      (node (ref "RESET_BUTTON") (pin "1") (pinfunction "1_1") (pintype "passive"))
      (node (ref "RESET_BUTTON") (pin "2") (pinfunction "2_2") (pintype "passive"))
      (node (ref "SENSOR2") (pin "1") (pinfunction "GND_1") (pintype "power_in"))
      (node (ref "SENSOR2") (pin "5") (pinfunction "SDO_5") (pintype "bidirectional"))
      (node (ref "SENSOR2") (pin "7") (pinfunction "GND_7") (pintype "power_in"))
      (node (ref "SJ1") (pin "1") (pinfunction "1_1") (pintype "passive"))
      (node (ref "TP4") (pin "TP") (pinfunction "TP_TP") (pintype "input"))
      (node (ref "TP5") (pin "TP") (pinfunction "TP_TP") (pintype "input"))
      (node (ref "U1") (pin "4") (pinfunction "GND_4") (pintype "power_in"))
      (node (ref "U1") (pin "9") (pinfunction "EXP_9") (pintype "passive"))
      (node (ref "U2") (pin "1") (pinfunction "GND_1") (pintype "power_in"))
      (node (ref "U2") (pin "28") (pinfunction "GND_28") (pintype "power_in"))
      (node (ref "U2") (pin "29_1") (pinfunction "GND_29_1") (pintype "power_in"))
      (node (ref "U2") (pin "29_2") (pinfunction "GND_29_2") (pintype "power_in"))
      (node (ref "U2") (pin "29_3") (pinfunction "GND_29_3") (pintype "power_in"))
      (node (ref "U2") (pin "29_4") (pinfunction "GND_29_4") (pintype "power_in"))
      (node (ref "U2") (pin "29_5") (pinfunction "GND_29_5") (pintype "power_in"))
      (node (ref "U2") (pin "29_6") (pinfunction "GND_29_6") (pintype "power_in"))
      (node (ref "U2") (pin "29_7") (pinfunction "GND_29_7") (pintype "power_in"))
      (node (ref "U2") (pin "29_8") (pinfunction "GND_29_8") (pintype "power_in"))
      (node (ref "U2") (pin "29_9") (pinfunction "GND_29_9") (pintype "power_in"))
      (node (ref "U3") (pin "13") (pinfunction "GND_13") (pintype "power_in"))
      (node (ref "U4") (pin "1") (pinfunction "CTG_1") (pintype "power_in"))
      (node (ref "U4") (pin "4") (pinfunction "GND_4") (pintype "power_in"))
      (node (ref "U4") (pin "6") (pinfunction "QSTRT_6") (pintype "input"))
      (node (ref "U4") (pin "9") (pinfunction "EP_9") (pintype "power_in"))
    )
    (net (code "15") (name "GPIO8") (class "Default")
      (node (ref "R1") (pin "2") (pinfunction "2_2") (pintype "passive"))
      (node (ref "U2") (pin "10") (pinfunction "IO8_10") (pintype "bidirectional"))
    )
    (net (code "16") (name "I2C_PW") (class "Default")
      (node (ref "C1") (pin "1") (pinfunction "1_1") (pintype "passive"))
      (node (ref "C2") (pin "1") (pinfunction "1_1") (pintype "passive"))
      (node (ref "R1-PINH") (pin "2") (pinfunction "2_2") (pintype "passive"))
      (node (ref "R2-PINH") (pin "2") (pinfunction "2_2") (pintype "passive"))
      (node (ref "SENSOR2") (pin "2") (pinfunction "CSB_2") (pintype "input"))
      (node (ref "SENSOR2") (pin "6") (pinfunction "VDDIO_6") (pintype "power_in"))
      (node (ref "SENSOR2") (pin "8") (pinfunction "VDD_8") (pintype "power_in"))
      (node (ref "U2") (pin "17") (pinfunction "IO19_17") (pintype "bidirectional"))
    )
    (net (code "17") (name "INT_RTC") (class "Default")
      (node (ref "R1_PINH1") (pin "1") (pinfunction "1_1") (pintype "passive"))
      (node (ref "TP15") (pin "TP") (pinfunction "TP_TP") (pintype "input"))
      (node (ref "U2") (pin "8") (pinfunction "IO0_8") (pintype "bidirectional"))
      (node (ref "U3") (pin "3") (pinfunction "SQW/~{INT}_3") (pintype "output"))
    )
    (net (code "18") (name "IO{slash}BOOT") (class "Default")
      (node (ref "BOOT_BUTTON") (pin "3") (pinfunction "3_3") (pintype "passive"))
      (node (ref "BOOT_BUTTON") (pin "4") (pinfunction "4_4") (pintype "passive"))
      (node (ref "C6") (pin "1") (pinfunction "1_1") (pintype "passive"))
      (node (ref "R_BOOT") (pin "2") (pinfunction "2_2") (pintype "passive"))
      (node (ref "U2") (pin "15") (pinfunction "IO9_15") (pintype "bidirectional"))
    )
    (net (code "19") (name "IO{slash}CHANGE") (class "Default")
      (node (ref "C10") (pin "1") (pinfunction "1_1") (pintype "passive"))
      (node (ref "CHANGE_BUTTON") (pin "3") (pinfunction "3_3") (pintype "passive"))
      (node (ref "CHANGE_BUTTON") (pin "4") (pinfunction "4_4") (pintype "passive"))
      (node (ref "R_CHANGE") (pin "2") (pinfunction "2_2") (pintype "passive"))
      (node (ref "U2") (pin "23") (pinfunction "IO15_23") (pintype "bidirectional"))
    )
    (net (code "20") (name "MISO") (class "Default")
      (node (ref "D12") (pin "2") (pinfunction "2_2") (pintype "passive"))
      (node (ref "J4") (pin "P7") (pinfunction "DAT0_P7") (pintype "bidirectional"))
      (node (ref "R8") (pin "1") (pinfunction "1_1") (pintype "passive"))
      (node (ref "TP6") (pin "TP") (pinfunction "TP_TP") (pintype "input"))
      (node (ref "U1") (pin "2") (pinfunction "DO(IO1)_2") (pintype "bidirectional"))
      (node (ref "U2") (pin "27") (pinfunction "IO2_27") (pintype "bidirectional"))
    )
    (net (code "21") (name "MOSI") (class "Default")
      (node (ref "D11") (pin "2") (pinfunction "2_2") (pintype "passive"))
      (node (ref "J1") (pin "14") (pinfunction "14_14") (pintype "bidirectional"))
      (node (ref "J4") (pin "P3") (pinfunction "CMD_P3") (pintype "bidirectional"))
      (node (ref "R7") (pin "1") (pinfunction "1_1") (pintype "passive"))
      (node (ref "TP7") (pin "TP") (pinfunction "TP_TP") (pintype "input"))
      (node (ref "U1") (pin "5") (pinfunction "DI(IO0)_5") (pintype "bidirectional"))
      (node (ref "U2") (pin "7") (pinfunction "IO7_7") (pintype "bidirectional"))
    )
    (net (code "22") (name "Net-(D2-CATHODE)") (class "Default")
      (node (ref "C1_BAT1") (pin "1") (pinfunction "1_1") (pintype "passive"))
      (node (ref "D2") (pin "1") (pinfunction "CATHODE_1") (pintype "bidirectional"))
      (node (ref "IC4") (pin "1") (pinfunction "VIN_1") (pintype "bidirectional"))
      (node (ref "IC4") (pin "3") (pinfunction "CE_3") (pintype "bidirectional"))
      (node (ref "Q1") (pin "2") (pinfunction "S_2") (pintype "bidirectional"))
    )
    (net (code "23") (name "Net-(D3-A)") (class "Default")
      (node (ref "C4") (pin "1") (pinfunction "1_1") (pintype "passive"))
      (node (ref "D3") (pin "2") (pinfunction "A_2") (pintype "bidirectional"))
      (node (ref "D4") (pin "1") (pinfunction "K_1") (pintype "bidirectional"))
    )
    (net (code "24") (name "Net-(D7-CATHODE)") (class "Default")
      (node (ref "D7") (pin "1") (pinfunction "CATHODE_1") (pintype "bidirectional"))
      (node (ref "R_CAPACITOR") (pin "2") (pinfunction "2_2") (pintype "passive"))
    )
    (net (code "25") (name "Net-(EPD_C1-Pad2)") (class "Default")
      (node (ref "EPD_C1") (pin "2") (pinfunction "2_2") (pintype "passive"))
      (node (ref "J1") (pin "4") (pinfunction "4_4") (pintype "bidirectional"))
    )
    (net (code "26") (name "Net-(EPD_C2-Pad2)") (class "Default")
      (node (ref "EPD_C2") (pin "2") (pinfunction "2_2") (pintype "passive"))
      (node (ref "J1") (pin "5") (pinfunction "5_5") (pintype "bidirectional"))
    )
    (net (code "27") (name "Net-(EPD_C6-Pad1)") (class "Default")
      (node (ref "EPD_C6") (pin "1") (pinfunction "1_1") (pintype "passive"))
      (node (ref "J1") (pin "18") (pinfunction "18_18") (pintype "bidirectional"))
    )
    (net (code "28") (name "Net-(EPD_C7-Pad1)") (class "Default")
      (node (ref "EPD_C7") (pin "1") (pinfunction "1_1") (pintype "passive"))
      (node (ref "J1") (pin "19") (pinfunction "19_19") (pintype "bidirectional"))
    )
    (net (code "29") (name "Net-(EPD_C8-Pad1)") (class "Default")
      (node (ref "EPD_C8") (pin "1") (pinfunction "1_1") (pintype "passive"))
      (node (ref "J1") (pin "20") (pinfunction "20_20") (pintype "bidirectional"))
    )
    (net (code "30") (name "Net-(EPD_C10-Pad1)") (class "Default")
      (node (ref "EPD_C10") (pin "1") (pinfunction "1_1") (pintype "passive"))
      (node (ref "J1") (pin "22") (pinfunction "22_22") (pintype "bidirectional"))
    )
    (net (code "31") (name "Net-(EPD_C12-Pad1)") (class "Default")
      (node (ref "EPD_C12") (pin "1") (pinfunction "1_1") (pintype "passive"))
      (node (ref "J1") (pin "24") (pinfunction "24_24") (pintype "bidirectional"))
    )
    (net (code "32") (name "Net-(GHC_LED-PadC)") (class "Default")
      (node (ref "GHC_LED") (pin "C") (pinfunction "C_C") (pintype "passive"))
      (node (ref "R1_BAT") (pin "2") (pinfunction "2_2") (pintype "passive"))
    )
    (net (code "33") (name "Net-(IC1-CT)") (class "Default")
      (node (ref "C_DELAY") (pin "1") (pinfunction "1_1") (pintype "passive"))
      (node (ref "IC1") (pin "5") (pinfunction "CT_5") (pintype "bidirectional"))
    )
    (net (code "34") (name "Net-(J2-PadA5)") (class "Default")
      (node (ref "J2") (pin "A5") (pinfunction "A5_A5") (pintype "bidirectional"))
      (node (ref "R2-USB1") (pin "2") (pinfunction "2_2") (pintype "passive"))
    )
    (net (code "35") (name "Net-(J2-PadB5)") (class "Default")
      (node (ref "J2") (pin "B5") (pinfunction "B5_B5") (pintype "bidirectional"))
      (node (ref "R2-USB") (pin "1") (pinfunction "1_1") (pintype "passive"))
    )
    (net (code "36") (name "Net-(MCP73831-PROG)") (class "Default")
      (node (ref "MCP73831") (pin "5") (pinfunction "PROG_5") (pintype "input"))
      (node (ref "R2_BAT") (pin "2") (pinfunction "2_2") (pintype "passive"))
    )
    (net (code "37") (name "Net-(MCP73831-STAT)") (class "Default")
      (node (ref "MCP73831") (pin "1") (pinfunction "STAT_1") (pintype "output"))
      (node (ref "R1_BAT") (pin "1") (pinfunction "1_1") (pintype "passive"))
    )
    (net (code "38") (name "PREVGH") (class "Default")
      (node (ref "D5") (pin "1") (pinfunction "K_1") (pintype "bidirectional"))
      (node (ref "EPD_C9") (pin "1") (pinfunction "1_1") (pintype "passive"))
      (node (ref "J1") (pin "21") (pinfunction "21_21") (pintype "bidirectional"))
    )
    (net (code "39") (name "PREVGL") (class "Default")
      (node (ref "D4") (pin "2") (pinfunction "A_2") (pintype "bidirectional"))
      (node (ref "EPD_C11") (pin "1") (pinfunction "1_1") (pintype "passive"))
      (node (ref "J1") (pin "23") (pinfunction "23_23") (pintype "bidirectional"))
    )
    (net (code "40") (name "RESE") (class "Default")
      (node (ref "J1") (pin "3") (pinfunction "3_3") (pintype "bidirectional"))
      (node (ref "Q3") (pin "2") (pinfunction "S_2") (pintype "bidirectional"))
      (node (ref "R3") (pin "1") (pinfunction "1_1") (pintype "passive"))
    )
    (net (code "41") (name "RESE'") (class "Default")
      (node (ref "R2") (pin "2") (pinfunction "2_2") (pintype "passive"))
      (node (ref "R3") (pin "2") (pinfunction "2_2") (pintype "passive"))
      (node (ref "SJ1") (pin "2") (pinfunction "2_2") (pintype "passive"))
    )
    (net (code "42") (name "RESET") (class "Default")
      (node (ref "C5") (pin "1") (pinfunction "1_1") (pintype "passive"))
      (node (ref "IC1") (pin "1") (pinfunction "VOUT_1") (pintype "bidirectional"))
      (node (ref "RESET_BUTTON") (pin "3") (pinfunction "3_3") (pintype "passive"))
      (node (ref "RESET_BUTTON") (pin "4") (pinfunction "4_4") (pintype "passive"))
      (node (ref "R_RESET") (pin "2") (pinfunction "2_2") (pintype "passive"))
      (node (ref "U2") (pin "3") (pinfunction "EN_3") (pintype "input"))
    )
    (net (code "43") (name "RTC_RST") (class "Default")
      (node (ref "U2") (pin "16") (pinfunction "IO18_16") (pintype "bidirectional"))
      (node (ref "U3") (pin "4") (pinfunction "~{RST}_4") (pintype "input"))
    )
    (net (code "44") (name "RX") (class "Default")
      (node (ref "TP2") (pin "TP") (pinfunction "TP_TP") (pintype "input"))
      (node (ref "U2") (pin "24") (pinfunction "RXD0/GPIO17_24") (pintype "bidirectional"))
    )
    (net (code "45") (name "SCK") (class "Default")
      (node (ref "D10") (pin "2") (pinfunction "2_2") (pintype "passive"))
      (node (ref "J1") (pin "13") (pinfunction "13_13") (pintype "bidirectional"))
      (node (ref "J4") (pin "P5") (pinfunction "CLK_P5") (pintype "bidirectional"))
      (node (ref "R6") (pin "1") (pinfunction "1_1") (pintype "passive"))
      (node (ref "TP8") (pin "TP") (pinfunction "TP_TP") (pintype "input"))
      (node (ref "U1") (pin "6") (pinfunction "CLK_6") (pintype "input"))
      (node (ref "U2") (pin "6") (pinfunction "IO6_6") (pintype "bidirectional"))
    )
    (net (code "46") (name "SCL") (class "Default")
      (node (ref "J3") (pin "4") (pinfunction "4_4") (pintype "passive"))
      (node (ref "R2-PINH") (pin "1") (pinfunction "1_1") (pintype "passive"))
      (node (ref "SENSOR2") (pin "4") (pinfunction "SCK_4") (pintype "input"))
      (node (ref "U2") (pin "20") (pinfunction "IO22_20") (pintype "bidirectional"))
      (node (ref "U3") (pin "16") (pinfunction "SCL_16") (pintype "input"))
      (node (ref "U4") (pin "7") (pinfunction "SCL_7") (pintype "input"))
    )
    (net (code "47") (name "SDA") (class "Default")
      (node (ref "J3") (pin "3") (pinfunction "3_3") (pintype "passive"))
      (node (ref "R1-PINH") (pin "1") (pinfunction "1_1") (pintype "passive"))
      (node (ref "SENSOR2") (pin "3") (pinfunction "SDI_3") (pintype "bidirectional"))
      (node (ref "U2") (pin "19") (pinfunction "IO21_19") (pintype "bidirectional"))
      (node (ref "U3") (pin "15") (pinfunction "SDA_15") (pintype "bidirectional"))
      (node (ref "U4") (pin "8") (pinfunction "SDA_8") (pintype "bidirectional"))
    )
    (net (code "48") (name "SRC") (class "Default")
      (node (ref "C4") (pin "2") (pinfunction "2_2") (pintype "passive"))
      (node (ref "D5") (pin "2") (pinfunction "A_2") (pintype "bidirectional"))
      (node (ref "L1") (pin "1") (pinfunction "1_1") (pintype "passive"))
      (node (ref "Q3") (pin "3") (pinfunction "D_3") (pintype "bidirectional"))
    )
    (net (code "49") (name "SS_SD") (class "Default")
      (node (ref "D8") (pin "2") (pinfunction "2_2") (pintype "passive"))
      (node (ref "J4") (pin "P2") (pinfunction "CD/DAT3_P2") (pintype "bidirectional"))
      (node (ref "R10") (pin "1") (pinfunction "1_1") (pintype "passive"))
      (node (ref "U2") (pin "4") (pinfunction "IO4_4") (pintype "bidirectional"))
    )
    (net (code "50") (name "TX") (class "Default")
      (node (ref "TP1") (pin "TP") (pinfunction "TP_TP") (pintype "input"))
      (node (ref "U2") (pin "25") (pinfunction "TXD0/GPIO16_25") (pintype "bidirectional"))
    )
    (net (code "51") (name "USB_D+") (class "Default")
      (node (ref "D1") (pin "1") (pinfunction "I/O1_1_1") (pintype "bidirectional"))
      (node (ref "U2") (pin "14") (pinfunction "IO13_14") (pintype "bidirectional"))
    )
    (net (code "52") (name "USB_D-") (class "Default")
      (node (ref "D1") (pin "3") (pinfunction "I/O2_1_3") (pintype "bidirectional"))
      (node (ref "U2") (pin "13") (pinfunction "IO12_13") (pintype "bidirectional"))
    )
    (net (code "53") (name "VBAT") (class "Default")
      (node (ref "C2_BAT") (pin "1") (pinfunction "1_1") (pintype "passive"))
      (node (ref "MCP73831") (pin "3") (pinfunction "VBAT_3") (pintype "power_in"))
      (node (ref "Q1") (pin "3") (pinfunction "D_3") (pintype "bidirectional"))
      (node (ref "TP3") (pin "TP") (pinfunction "TP_TP") (pintype "input"))
      (node (ref "U4") (pin "2") (pinfunction "CELL_2") (pintype "power_in"))
      (node (ref "U4") (pin "3") (pinfunction "VDD_3") (pintype "power_in"))
    )
    (net (code "54") (name "VBUS") (class "Default")
      (node (ref "C1_BAT") (pin "1") (pinfunction "1_1") (pintype "passive"))
      (node (ref "C4_USB") (pin "1") (pinfunction "1_1") (pintype "passive"))
      (node (ref "C5_USB") (pin "1") (pinfunction "1_1") (pintype "passive"))
      (node (ref "D1") (pin "5") (pinfunction "VBUS_5") (pintype "bidirectional"))
      (node (ref "D2") (pin "2") (pinfunction "ANODE_2") (pintype "bidirectional"))
      (node (ref "GHC_LED") (pin "A") (pinfunction "A_A") (pintype "passive"))
      (node (ref "MCP73831") (pin "4") (pinfunction "VIN_4") (pintype "power_in"))
      (node (ref "PFMF.050.1") (pin "2") (pinfunction "2_2") (pintype "passive"))
      (node (ref "Q1") (pin "1") (pinfunction "G_1") (pintype "bidirectional"))
      (node (ref "R1_PWRUSB") (pin "2") (pinfunction "2_2") (pintype "passive"))
      (node (ref "TP14") (pin "TP") (pinfunction "TP_TP") (pintype "input"))
    )
    (net (code "55") (name "VRTC") (class "Default")
      (node (ref "C10_SUPERCAP") (pin "2") (pinfunction "2_2") (pintype "passive"))
      (node (ref "C8") (pin "1") (pinfunction "1_1") (pintype "passive"))
      (node (ref "R_CAPACITOR") (pin "1") (pinfunction "1_1") (pintype "passive"))
      (node (ref "U3") (pin "14") (pinfunction "VBAT_14") (pintype "power_in"))
    )
    (net (code "56") (name "unconnected-(IC1-NC-Pad4)") (class "Default")
      (node (ref "IC1") (pin "4") (pinfunction "NC_4") (pintype "no_connect"))
    )
    (net (code "57") (name "unconnected-(IC4-NC-Pad4)") (class "Default")
      (node (ref "IC4") (pin "4") (pinfunction "NC_4") (pintype "no_connect"))
    )
    (net (code "58") (name "unconnected-(J1-Pad1)") (class "Default")
      (node (ref "J1") (pin "1") (pinfunction "1_1") (pintype "bidirectional"))
    )
    (net (code "59") (name "unconnected-(J1-Pad6)") (class "Default")
      (node (ref "J1") (pin "6") (pinfunction "6_6") (pintype "bidirectional"))
    )
    (net (code "60") (name "unconnected-(J1-Pad7)") (class "Default")
      (node (ref "J1") (pin "7") (pinfunction "7_7") (pintype "bidirectional"))
    )
    (net (code "61") (name "unconnected-(J2-PadA8)") (class "Default")
      (node (ref "J2") (pin "A8") (pinfunction "A8_A8") (pintype "bidirectional"))
    )
    (net (code "62") (name "unconnected-(J2-PadB8)") (class "Default")
      (node (ref "J2") (pin "B8") (pinfunction "B8_B8") (pintype "bidirectional"))
    )
    (net (code "63") (name "unconnected-(J4-DAT1-PadP8)") (class "Default")
      (node (ref "J4") (pin "P8") (pinfunction "DAT1_P8") (pintype "bidirectional"))
    )
    (net (code "64") (name "unconnected-(J4-DAT2-PadP1)") (class "Default")
      (node (ref "J4") (pin "P1") (pinfunction "DAT2_P1") (pintype "bidirectional"))
    )
    (net (code "65") (name "unconnected-(J4-DETECTION_1-PadS1)") (class "Default")
      (node (ref "J4") (pin "S1") (pinfunction "DETECTION_1_S1") (pintype "bidirectional"))
    )
    (net (code "66") (name "unconnected-(J4-DETECTION_2-PadS2)") (class "Default")
      (node (ref "J4") (pin "S2") (pinfunction "DETECTION_2_S2") (pintype "bidirectional"))
    )
    (net (code "67") (name "unconnected-(U2-NC-Pad22)") (class "Default")
      (node (ref "U2") (pin "22") (pinfunction "NC_22") (pintype "no_connect"))
    )
    (net (code "68") (name "unconnected-(U4-~{ALERT}-Pad5)") (class "Default")
      (node (ref "U4") (pin "5") (pinfunction "~{ALERT}_5") (pintype "output"))
    )
  )
)
